# SCH_usb-hub_2024-08-24.net
KiCad netlist of a schematic drawn in EasyEDA
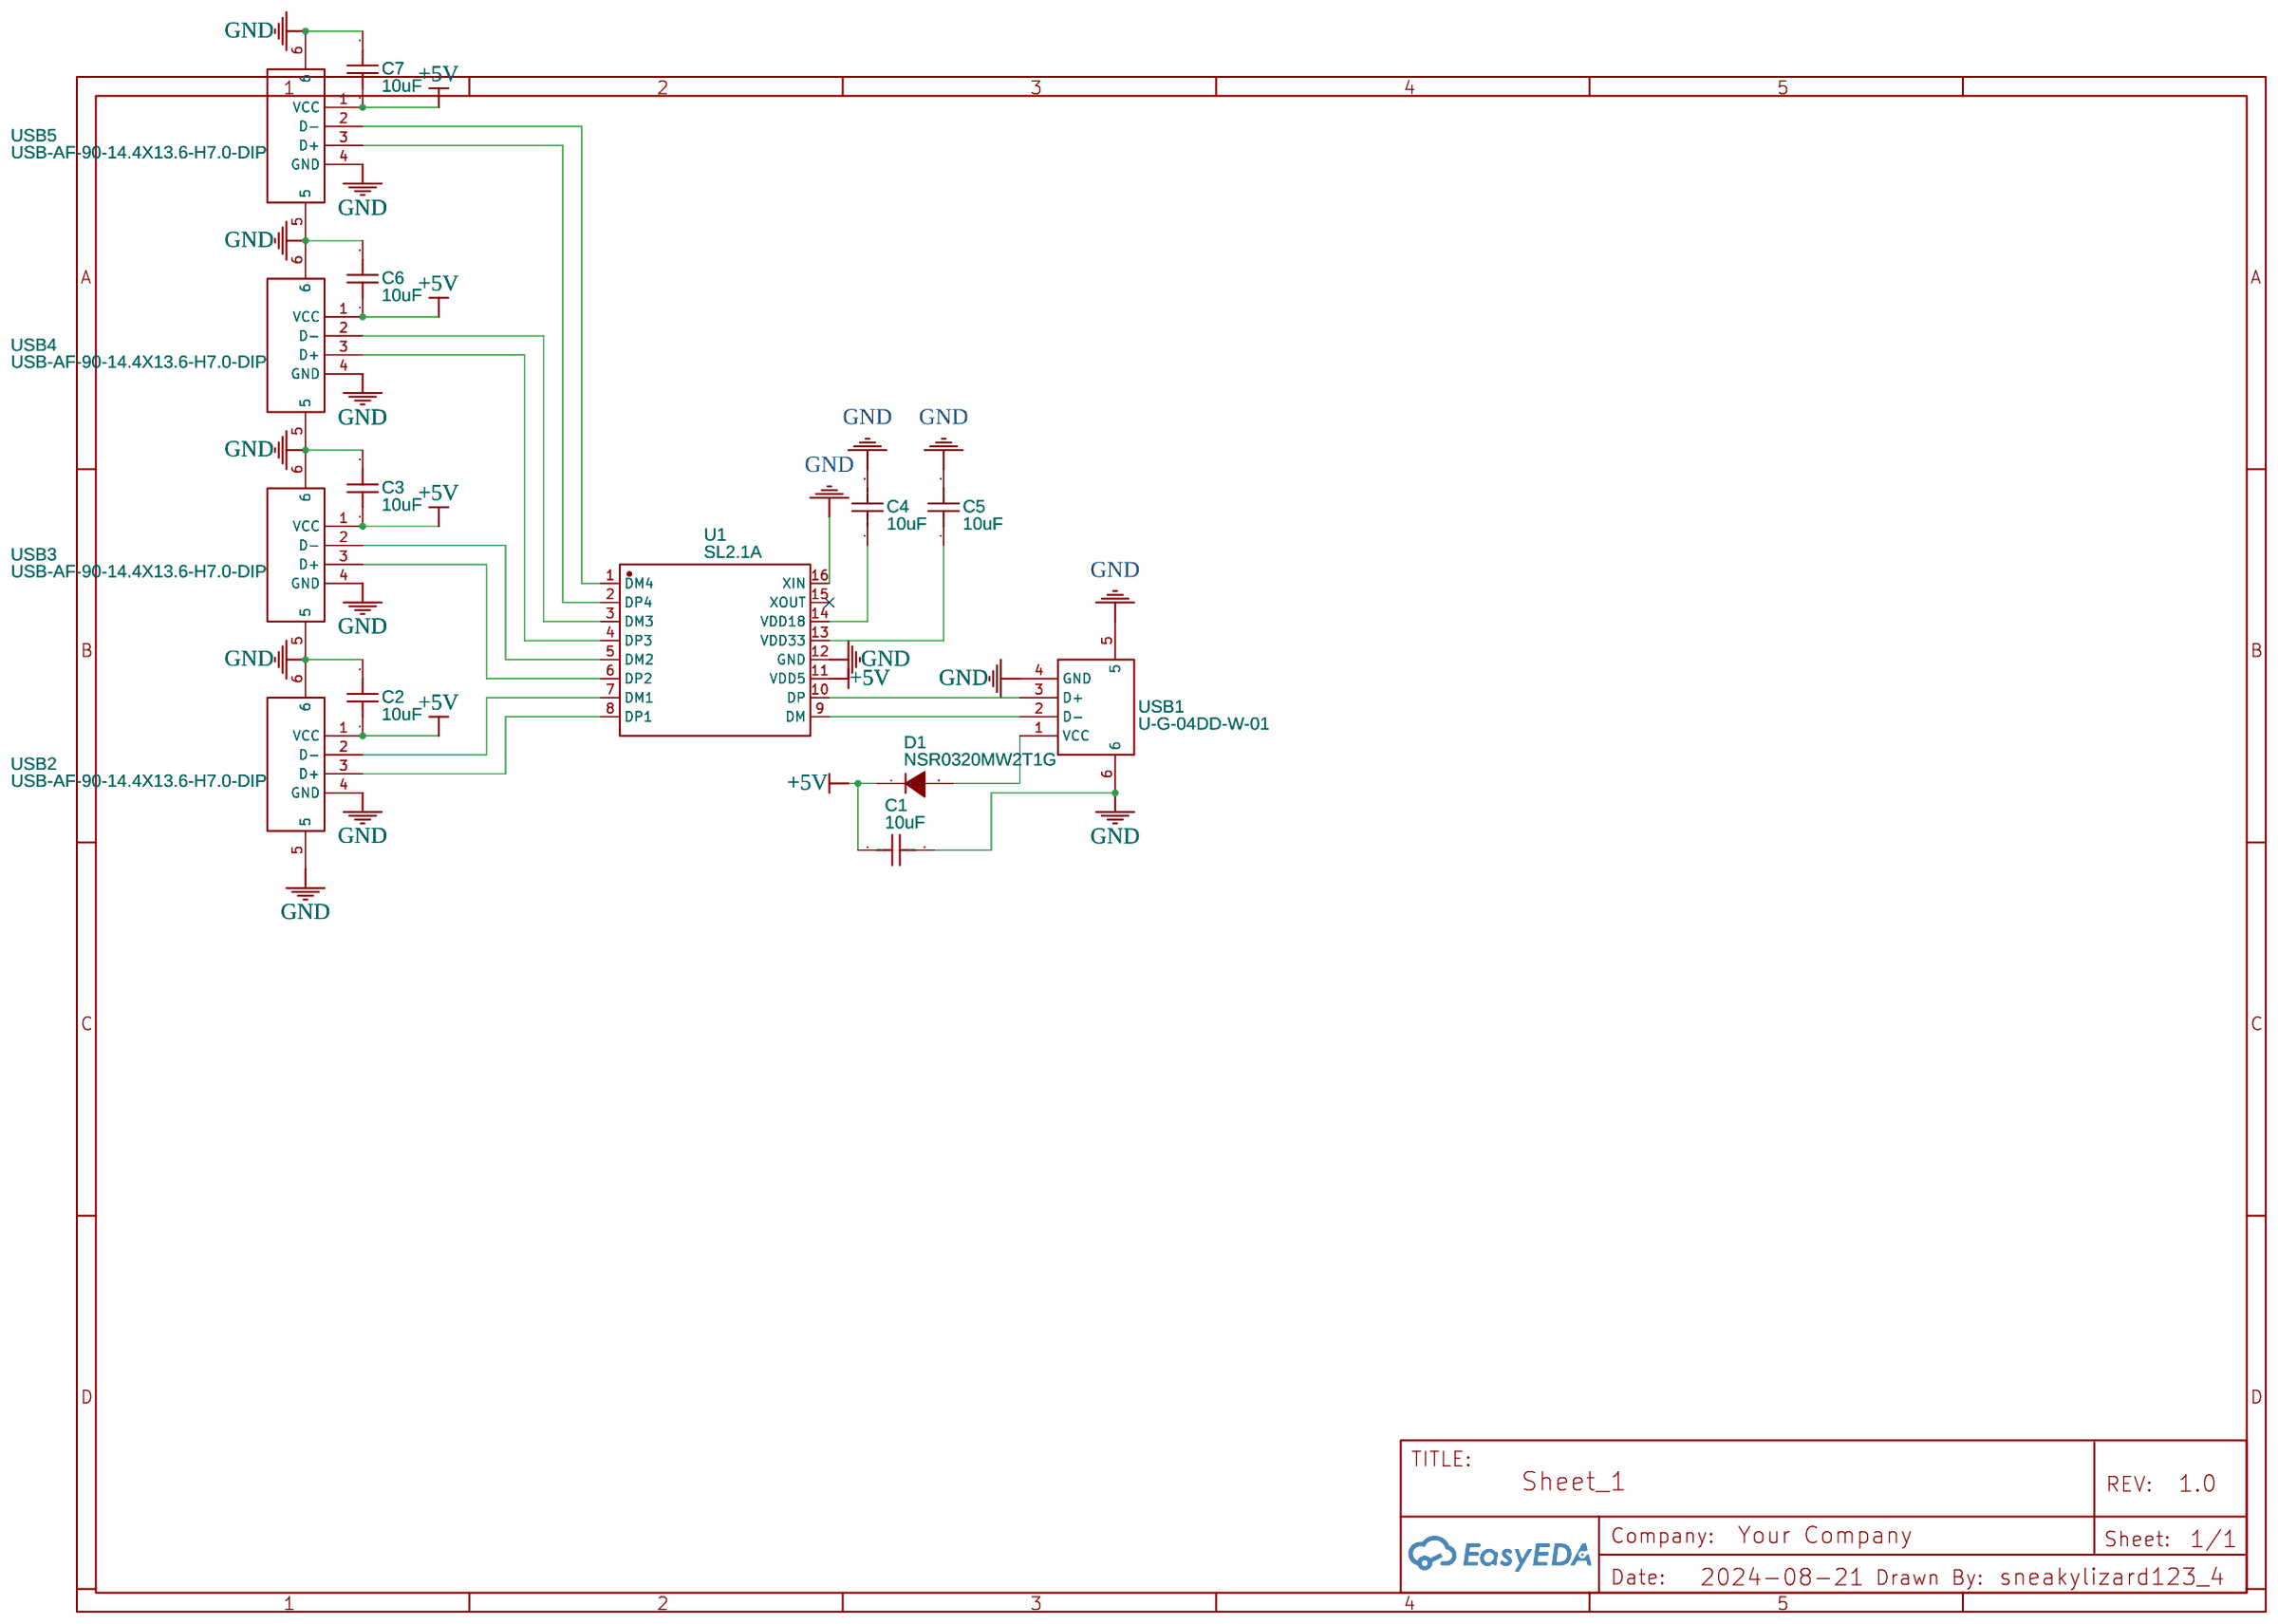
[diagram p0: schematic sheet]

(export (version "E")
  (design (tool "Eeschema 10.0.6"))
  (components
    (comp (ref "C1")
      (value "10uF")
      (fields
        (field (name "Manufacturer Part") "CL10A106KP8NNNC")
        (field (name "Manufacturer") "SAMSUNG(三星)")
      )
      (libsource (lib "") (part "CL10A106KP8NNNC_1"))
    )
    (comp (ref "C2")
      (value "10uF")
      (fields
        (field (name "Manufacturer Part") "CL10A106KP8NNNC")
        (field (name "Manufacturer") "SAMSUNG(三星)")
      )
      (libsource (lib "") (part "CL10A106KP8NNNC"))
    )
    (comp (ref "C3")
      (value "10uF")
      (fields
        (field (name "Manufacturer Part") "CL10A106KP8NNNC")
        (field (name "Manufacturer") "SAMSUNG(三星)")
      )
      (libsource (lib "") (part "CL10A106KP8NNNC"))
    )
    (comp (ref "C4")
      (value "10uF")
      (fields
        (field (name "Manufacturer Part") "CL10A106KP8NNNC")
        (field (name "Manufacturer") "SAMSUNG(三星)")
      )
      (libsource (lib "") (part "CL10A106KP8NNNC"))
    )
    (comp (ref "C5")
      (value "10uF")
      (fields
        (field (name "Manufacturer Part") "CL10A106KP8NNNC")
        (field (name "Manufacturer") "SAMSUNG(三星)")
      )
      (libsource (lib "") (part "CL10A106KP8NNNC"))
    )
    (comp (ref "C6")
      (value "10uF")
      (fields
        (field (name "Manufacturer Part") "CL10A106KP8NNNC")
        (field (name "Manufacturer") "SAMSUNG(三星)")
      )
      (libsource (lib "") (part "CL10A106KP8NNNC"))
    )
    (comp (ref "C7")
      (value "10uF")
      (fields
        (field (name "Manufacturer Part") "CL10A106KP8NNNC")
        (field (name "Manufacturer") "SAMSUNG(三星)")
      )
      (libsource (lib "") (part "CL10A106KP8NNNC"))
    )
    (comp (ref "D1")
      (value "NSR0320MW2T1G")
      (fields (field (name "Manufacturer") "onsemi(安森美)"))
      (libsource (lib "") (part "NSR0320MW2T1G"))
    )
    (comp (ref "U1")
      (value "SL2.1A")
      (fields (field (name "Manufacturer") "CoreChips(和芯润德)"))
      (libsource (lib "") (part "SL2.1A"))
    )
    (comp (ref "USB1")
      (value "U-G-04DD-W-01")
      (fields (field (name "Manufacturer Part") "U-G-O4DD-W-1") (field (name "Manufacturer") "韩国韩荣"))
      (libsource (lib "") (part "U-G-04DD-W-01"))
    )
    (comp (ref "USB2")
      (value "USB-AF-90-14.4X13.6-H7.0-DIP")
      (fields (field (name "Manufacturer Part") "903-131A1011D10100") (field (name "Manufacturer") "精拓金"))
      (libsource (lib "") (part "USB-AF-90-14.4X13.6-H7.0-DIP"))
    )
    (comp (ref "USB3")
      (value "USB-AF-90-14.4X13.6-H7.0-DIP")
      (fields (field (name "Manufacturer Part") "903-131A1011D10100") (field (name "Manufacturer") "精拓金"))
      (libsource (lib "") (part "USB-AF-90-14.4X13.6-H7.0-DIP"))
    )
    (comp (ref "USB4")
      (value "USB-AF-90-14.4X13.6-H7.0-DIP")
      (fields (field (name "Manufacturer Part") "903-131A1011D10100") (field (name "Manufacturer") "精拓金"))
      (libsource (lib "") (part "USB-AF-90-14.4X13.6-H7.0-DIP"))
    )
    (comp (ref "USB5")
      (value "USB-AF-90-14.4X13.6-H7.0-DIP")
      (fields (field (name "Manufacturer Part") "903-131A1011D10100") (field (name "Manufacturer") "精拓金"))
      (libsource (lib "") (part "USB-AF-90-14.4X13.6-H7.0-DIP"))
    )
  )
  (nets
    (net (code "1") (name "+5V") (class "Default")
      (node (ref "C1") (pin "1") (pinfunction "1_1") (pintype "unspecified"))
      (node (ref "C2") (pin "1") (pinfunction "1_1") (pintype "unspecified"))
      (node (ref "C3") (pin "1") (pinfunction "1_1") (pintype "unspecified"))
      (node (ref "C6") (pin "1") (pinfunction "1_1") (pintype "unspecified"))
      (node (ref "C7") (pin "1") (pinfunction "1_1") (pintype "unspecified"))
      (node (ref "D1") (pin "1") (pinfunction "C_1") (pintype "unspecified"))
      (node (ref "U1") (pin "11") (pinfunction "VDD5_11") (pintype "unspecified"))
      (node (ref "USB2") (pin "1") (pinfunction "VCC_1") (pintype "unspecified"))
      (node (ref "USB3") (pin "1") (pinfunction "VCC_1") (pintype "unspecified"))
      (node (ref "USB4") (pin "1") (pinfunction "VCC_1") (pintype "unspecified"))
      (node (ref "USB5") (pin "1") (pinfunction "VCC_1") (pintype "unspecified"))
    )
    (net (code "2") (name "GND") (class "Default")
      (node (ref "C1") (pin "2") (pinfunction "2_2") (pintype "unspecified"))
      (node (ref "C2") (pin "2") (pinfunction "2_2") (pintype "unspecified"))
      (node (ref "C3") (pin "2") (pinfunction "2_2") (pintype "unspecified"))
      (node (ref "C4") (pin "2") (pinfunction "2_2") (pintype "unspecified"))
      (node (ref "C5") (pin "2") (pinfunction "2_2") (pintype "unspecified"))
      (node (ref "C6") (pin "2") (pinfunction "2_2") (pintype "unspecified"))
      (node (ref "C7") (pin "2") (pinfunction "2_2") (pintype "unspecified"))
      (node (ref "U1") (pin "12") (pinfunction "GND_12") (pintype "unspecified"))
      (node (ref "U1") (pin "16") (pinfunction "XIN_16") (pintype "unspecified"))
      (node (ref "USB1") (pin "4") (pinfunction "GND_4") (pintype "unspecified"))
      (node (ref "USB1") (pin "5") (pinfunction "5_5") (pintype "unspecified"))
      (node (ref "USB1") (pin "6") (pinfunction "6_6") (pintype "unspecified"))
      (node (ref "USB2") (pin "4") (pinfunction "GND_4") (pintype "unspecified"))
      (node (ref "USB2") (pin "5") (pinfunction "5_5") (pintype "unspecified"))
      (node (ref "USB2") (pin "6") (pinfunction "6_6") (pintype "unspecified"))
      (node (ref "USB3") (pin "4") (pinfunction "GND_4") (pintype "unspecified"))
      (node (ref "USB3") (pin "5") (pinfunction "5_5") (pintype "unspecified"))
      (node (ref "USB3") (pin "6") (pinfunction "6_6") (pintype "unspecified"))
      (node (ref "USB4") (pin "4") (pinfunction "GND_4") (pintype "unspecified"))
      (node (ref "USB4") (pin "5") (pinfunction "5_5") (pintype "unspecified"))
      (node (ref "USB4") (pin "6") (pinfunction "6_6") (pintype "unspecified"))
      (node (ref "USB5") (pin "4") (pinfunction "GND_4") (pintype "unspecified"))
      (node (ref "USB5") (pin "5") (pinfunction "5_5") (pintype "unspecified"))
      (node (ref "USB5") (pin "6") (pinfunction "6_6") (pintype "unspecified"))
    )
    (net (code "3") (name "Net-(D1-A)") (class "Default")
      (node (ref "D1") (pin "2") (pinfunction "A_2") (pintype "unspecified"))
      (node (ref "USB1") (pin "1") (pinfunction "VCC_1") (pintype "unspecified"))
    )
    (net (code "4") (name "Net-(U1-DM)") (class "Default")
      (node (ref "U1") (pin "9") (pinfunction "DM_9") (pintype "unspecified"))
      (node (ref "USB1") (pin "2") (pinfunction "D-_2") (pintype "unspecified"))
    )
    (net (code "5") (name "Net-(U1-DM1)") (class "Default")
      (node (ref "U1") (pin "7") (pinfunction "DM1_7") (pintype "unspecified"))
      (node (ref "USB2") (pin "2") (pinfunction "D-_2") (pintype "unspecified"))
    )
    (net (code "6") (name "Net-(U1-DM2)") (class "Default")
      (node (ref "U1") (pin "5") (pinfunction "DM2_5") (pintype "unspecified"))
      (node (ref "USB3") (pin "2") (pinfunction "D-_2") (pintype "unspecified"))
    )
    (net (code "7") (name "Net-(U1-DM3)") (class "Default")
      (node (ref "U1") (pin "3") (pinfunction "DM3_3") (pintype "unspecified"))
      (node (ref "USB4") (pin "2") (pinfunction "D-_2") (pintype "unspecified"))
    )
    (net (code "8") (name "Net-(U1-DM4)") (class "Default")
      (node (ref "U1") (pin "1") (pinfunction "DM4_1") (pintype "unspecified"))
      (node (ref "USB5") (pin "2") (pinfunction "D-_2") (pintype "unspecified"))
    )
    (net (code "9") (name "Net-(U1-DP)") (class "Default")
      (node (ref "U1") (pin "10") (pinfunction "DP_10") (pintype "unspecified"))
      (node (ref "USB1") (pin "3") (pinfunction "D+_3") (pintype "unspecified"))
    )
    (net (code "10") (name "Net-(U1-DP1)") (class "Default")
      (node (ref "U1") (pin "8") (pinfunction "DP1_8") (pintype "unspecified"))
      (node (ref "USB2") (pin "3") (pinfunction "D+_3") (pintype "unspecified"))
    )
    (net (code "11") (name "Net-(U1-DP2)") (class "Default")
      (node (ref "U1") (pin "6") (pinfunction "DP2_6") (pintype "unspecified"))
      (node (ref "USB3") (pin "3") (pinfunction "D+_3") (pintype "unspecified"))
    )
    (net (code "12") (name "Net-(U1-DP3)") (class "Default")
      (node (ref "U1") (pin "4") (pinfunction "DP3_4") (pintype "unspecified"))
      (node (ref "USB4") (pin "3") (pinfunction "D+_3") (pintype "unspecified"))
    )
    (net (code "13") (name "Net-(U1-DP4)") (class "Default")
      (node (ref "U1") (pin "2") (pinfunction "DP4_2") (pintype "unspecified"))
      (node (ref "USB5") (pin "3") (pinfunction "D+_3") (pintype "unspecified"))
    )
    (net (code "14") (name "Net-(U1-VDD18)") (class "Default")
      (node (ref "C4") (pin "1") (pinfunction "1_1") (pintype "unspecified"))
      (node (ref "U1") (pin "14") (pinfunction "VDD18_14") (pintype "unspecified"))
    )
    (net (code "15") (name "Net-(U1-VDD33)") (class "Default")
      (node (ref "C5") (pin "1") (pinfunction "1_1") (pintype "unspecified"))
      (node (ref "U1") (pin "13") (pinfunction "VDD33_13") (pintype "unspecified"))
    )
    (net (code "16") (name "unconnected-(U1-XOUT-Pad15)") (class "Default")
      (node (ref "U1") (pin "15") (pinfunction "XOUT_15") (pintype "unspecified+no_connect"))
    )
  )
)
